# kick_2021_03.net
KiCad netlist of a schematic drawn in EAGLE
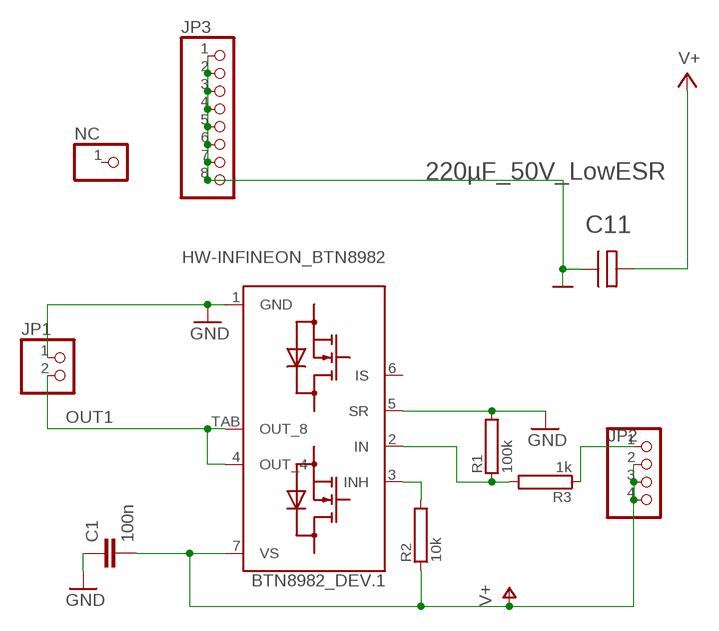
[diagram p0: schematic, sheet 1]

(export (version "E")
  (design (tool "Eeschema 10.0.6"))
  (components
    (comp (ref "BTN8982_DEV.1")
      (value "HW-INFINEON_BTN8982")
      (footprint "eagle-import:HW-INFINEON_TO263-7-1")
      (libsource (lib "eagle-import") (part "HW-INFINEON_BTN8962TA"))
    )
    (comp (ref "C1")
      (value "100n")
      (footprint "eagle-import:0603-CAP")
      (libsource (lib "eagle-import") (part "CAP0603-CAP"))
    )
    (comp (ref "C11")
      (value "220µF_50V_LowESR")
      (footprint "eagle-import:470µF_SMD_16V")
      (libsource (lib "eagle-import") (part "470µFSMD"))
    )
    (comp (ref "JP1")
      (value "PINHD-1X2/90")
      (footprint "eagle-import:1X02_90")
      (libsource (lib "eagle-import") (part "PINHD-1X2/90"))
    )
    (comp (ref "JP2")
      (value "PINHD-1X4")
      (footprint "eagle-import:1X04")
      (libsource (lib "eagle-import") (part "PINHD-1X4"))
    )
    (comp (ref "JP3")
      (value "PINHD-1X8")
      (footprint "eagle-import:1X08")
      (libsource (lib "eagle-import") (part "PINHD-1X8"))
    )
    (comp (ref "NC")
      (value "PINHD-1X1")
      (footprint "eagle-import:1X01")
      (libsource (lib "eagle-import") (part "PINHD-1X1"))
    )
    (comp (ref "R1")
      (value "100k")
      (footprint "eagle-import:0603")
      (libsource (lib "eagle-import") (part "06030603"))
    )
    (comp (ref "R2")
      (value "10k")
      (footprint "eagle-import:0603")
      (libsource (lib "eagle-import") (part "06030603"))
    )
    (comp (ref "R3")
      (value "1k")
      (footprint "eagle-import:0603")
      (libsource (lib "eagle-import") (part "06030603"))
    )
  )
  (nets
    (net (code "1") (name "/OUT1") (class "Default")
      (node (ref "BTN8982_DEV.1") (pin "4") (pinfunction "OUT_4_4") (pintype "output"))
      (node (ref "BTN8982_DEV.1") (pin "TAB") (pinfunction "OUT_8_TAB") (pintype "output"))
      (node (ref "JP1") (pin "2") (pinfunction "2_2") (pintype "passive"))
    )
    (net (code "2") (name "GND") (class "Default")
      (node (ref "BTN8982_DEV.1") (pin "1") (pinfunction "GND_1") (pintype "input"))
      (node (ref "BTN8982_DEV.1") (pin "5") (pinfunction "SR_5") (pintype "bidirectional"))
      (node (ref "C1") (pin "1") (pinfunction "1_1") (pintype "passive"))
      (node (ref "C11") (pin "-") (pinfunction "-_-") (pintype "passive"))
      (node (ref "JP1") (pin "1") (pinfunction "1_1") (pintype "passive"))
      (node (ref "JP3") (pin "1") (pinfunction "1_1") (pintype "passive"))
      (node (ref "JP3") (pin "2") (pinfunction "2_2") (pintype "passive"))
      (node (ref "JP3") (pin "3") (pinfunction "3_3") (pintype "passive"))
      (node (ref "JP3") (pin "4") (pinfunction "4_4") (pintype "passive"))
      (node (ref "JP3") (pin "5") (pinfunction "5_5") (pintype "passive"))
      (node (ref "JP3") (pin "6") (pinfunction "6_6") (pintype "passive"))
      (node (ref "JP3") (pin "7") (pinfunction "7_7") (pintype "passive"))
      (node (ref "JP3") (pin "8") (pinfunction "8_8") (pintype "passive"))
      (node (ref "R1") (pin "2") (pinfunction "2_2") (pintype "passive"))
    )
    (net (code "3") (name "Net-(BTN8982_DEV.1-IN)") (class "Default")
      (node (ref "BTN8982_DEV.1") (pin "2") (pinfunction "IN_2") (pintype "input"))
      (node (ref "R1") (pin "1") (pinfunction "1_1") (pintype "passive"))
      (node (ref "R3") (pin "2") (pinfunction "2_2") (pintype "passive"))
    )
    (net (code "4") (name "Net-(BTN8982_DEV.1-INH)") (class "Default")
      (node (ref "BTN8982_DEV.1") (pin "3") (pinfunction "INH_3") (pintype "bidirectional"))
      (node (ref "R2") (pin "2") (pinfunction "2_2") (pintype "passive"))
    )
    (net (code "5") (name "Net-(JP2-Pad1)") (class "Default")
      (node (ref "JP2") (pin "1") (pinfunction "1_1") (pintype "passive"))
      (node (ref "R3") (pin "1") (pinfunction "1_1") (pintype "passive"))
    )
    (net (code "6") (name "V+") (class "Default")
      (node (ref "BTN8982_DEV.1") (pin "7") (pinfunction "VS_7") (pintype "power_in"))
      (node (ref "C1") (pin "2") (pinfunction "2_2") (pintype "passive"))
      (node (ref "C11") (pin "+") (pinfunction "+_+") (pintype "passive"))
      (node (ref "JP2") (pin "2") (pinfunction "2_2") (pintype "passive"))
      (node (ref "JP2") (pin "3") (pinfunction "3_3") (pintype "passive"))
      (node (ref "JP2") (pin "4") (pinfunction "4_4") (pintype "passive"))
      (node (ref "R2") (pin "1") (pinfunction "1_1") (pintype "passive"))
    )
    (net (code "7") (name "unconnected-(BTN8982_DEV.1-IS-Pad6)") (class "Default")
      (node (ref "BTN8982_DEV.1") (pin "6") (pinfunction "IS_6") (pintype "bidirectional"))
    )
    (net (code "8") (name "unconnected-(NC-Pad1)") (class "Default")
      (node (ref "NC") (pin "1") (pinfunction "1_1") (pintype "passive"))
    )
  )
)
